# maxwell.net
KiCad netlist of a schematic drawn in EAGLE
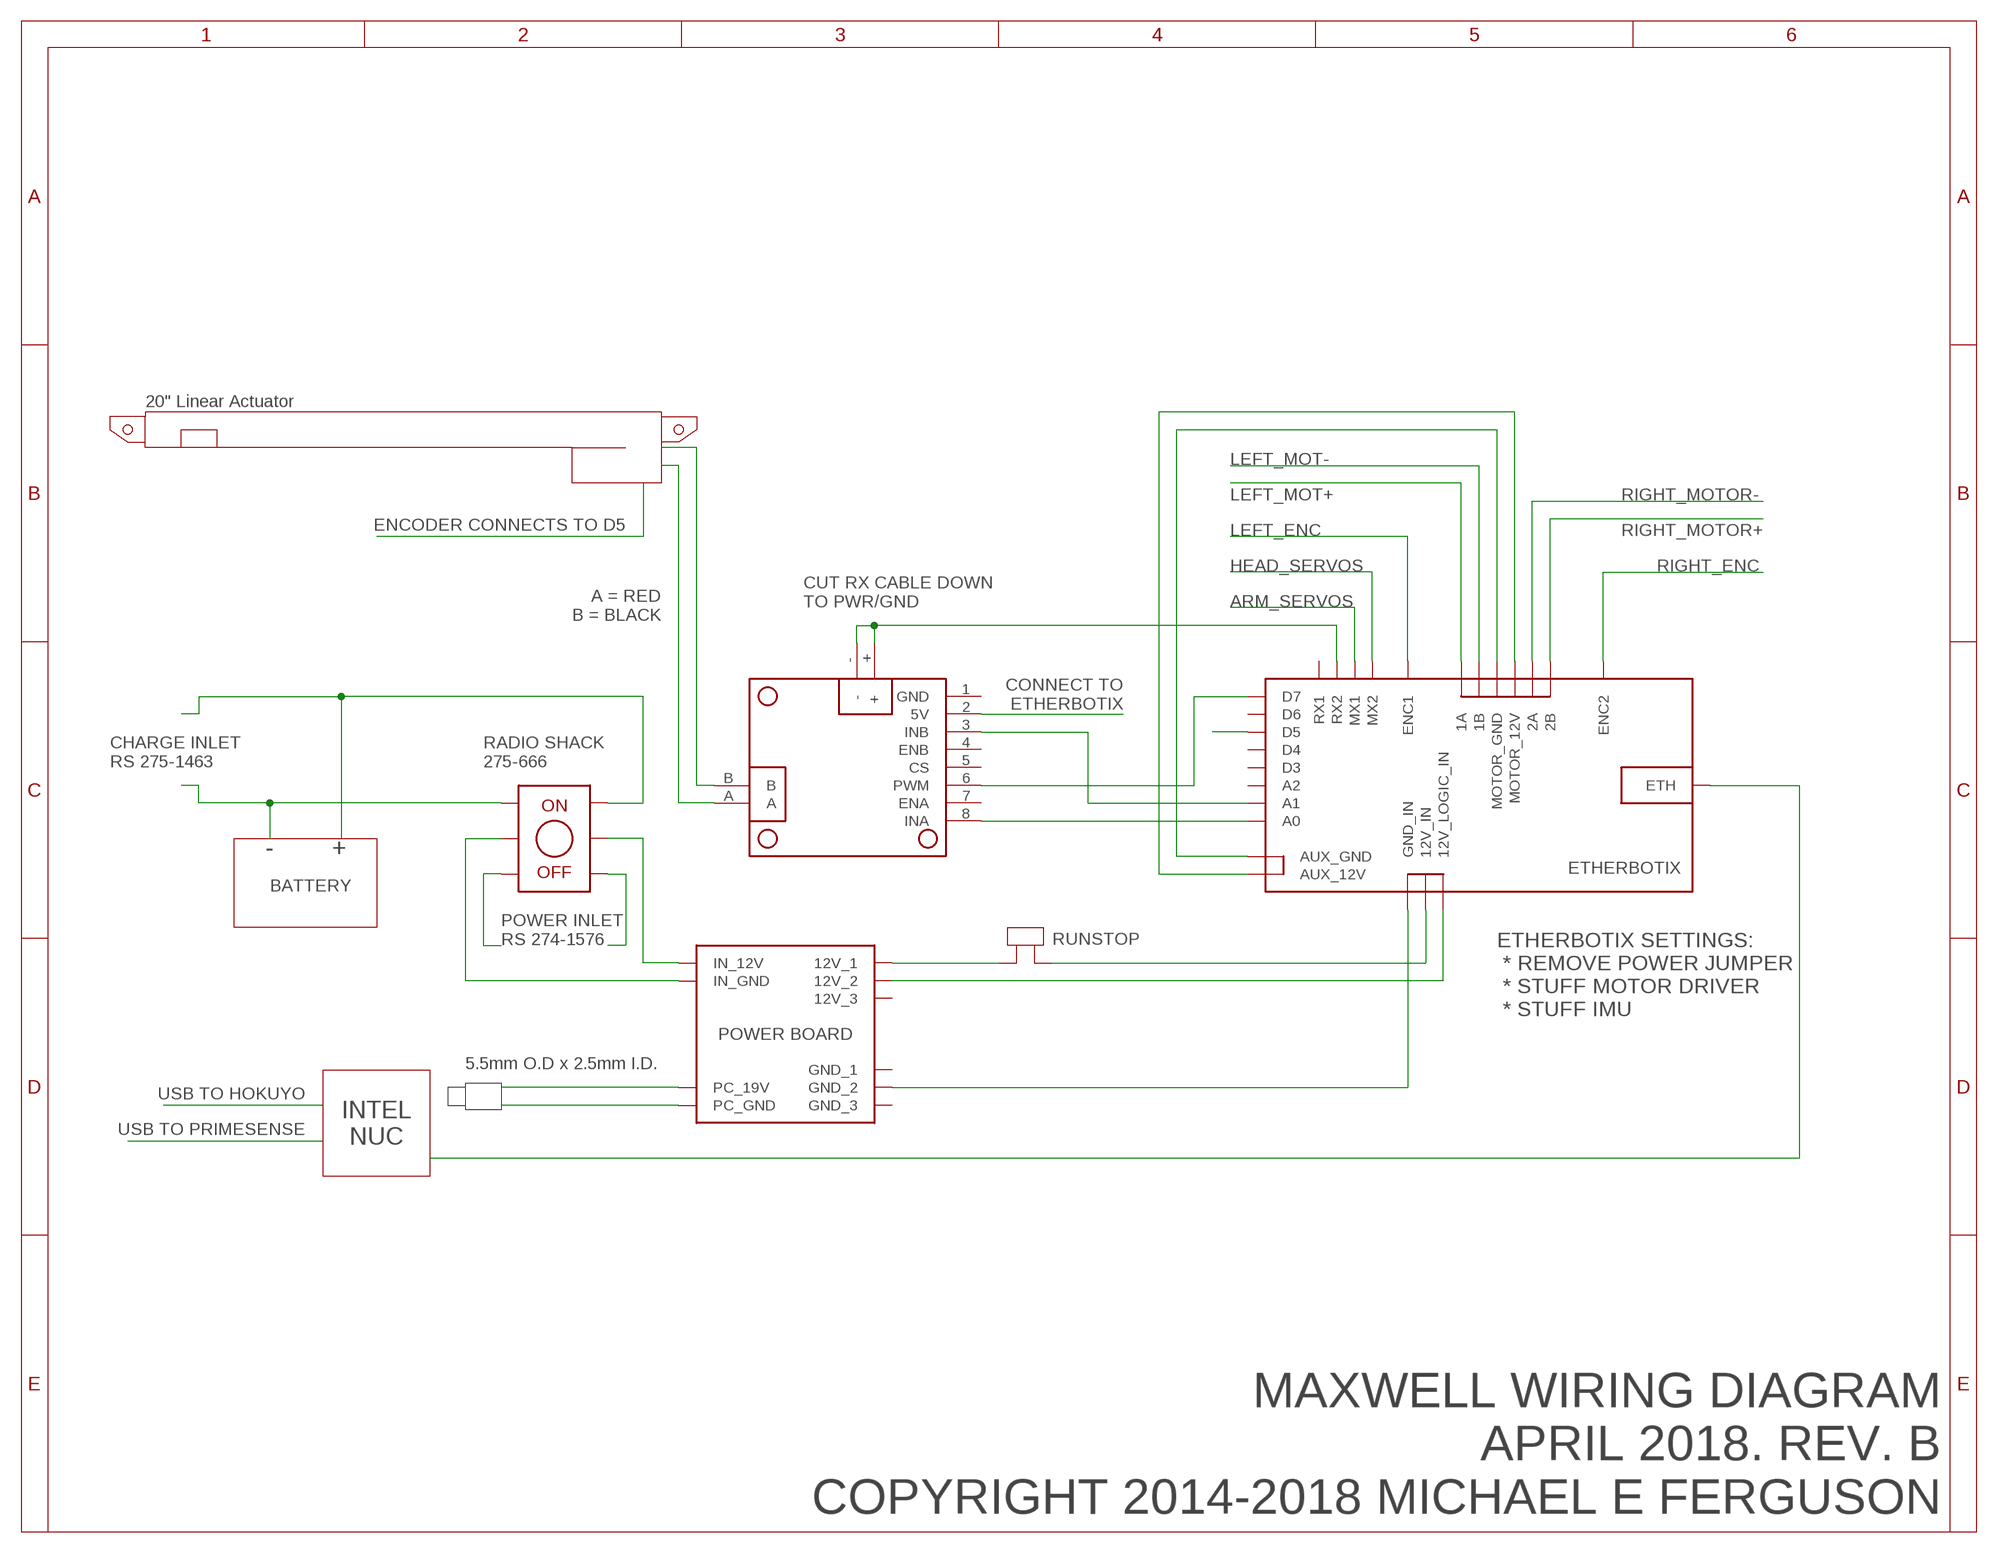
[diagram p0: schematic, sheet 1]

(export (version "E")
  (design (tool "Eeschema 10.0.6"))
  (components
    (comp (ref "U$1")
      (value "ETHERBOTIX")
      (footprint "eagle-import:CRAP")
      (libsource (lib "eagle-import") (part "ETHERBOTIX"))
    )
    (comp (ref "U$2")
      (value "MAXWELL_POWERBOARD")
      (footprint "eagle-import:CRAP")
      (libsource (lib "eagle-import") (part "MAXWELL_POWERBOARD"))
    )
    (comp (ref "U$3")
      (value "RS275-666")
      (footprint "eagle-import:CRAP")
      (libsource (lib "eagle-import") (part "RS275-666"))
    )
    (comp (ref "U$4")
      (value "MD01B")
      (footprint "eagle-import:MD01B")
      (libsource (lib "eagle-import") (part "MD01B"))
    )
  )
  (nets
    (net (code "1") (name "/ARM_SERVOS") (class "Default")
      (node (ref "U$1") (pin "P$23") (pinfunction "MX1_P$23") (pintype "bidirectional"))
    )
    (net (code "2") (name "/HEAD_SERVOS") (class "Default")
      (node (ref "U$1") (pin "P$24") (pinfunction "MX2_P$24") (pintype "bidirectional"))
    )
    (net (code "3") (name "/LEFT_ENC") (class "Default")
      (node (ref "U$1") (pin "P$17") (pinfunction "ENC1_P$17") (pintype "bidirectional"))
    )
    (net (code "4") (name "/LEFT_MOT+") (class "Default")
      (node (ref "U$1") (pin "P$1") (pinfunction "1A_P$1") (pintype "bidirectional"))
    )
    (net (code "5") (name "/LEFT_MOT-") (class "Default")
      (node (ref "U$1") (pin "P$2") (pinfunction "1B_P$2") (pintype "bidirectional"))
    )
    (net (code "6") (name "/RIGHT_ENC") (class "Default")
      (node (ref "U$1") (pin "P$18") (pinfunction "ENC2_P$18") (pintype "bidirectional"))
    )
    (net (code "7") (name "/RIGHT_MOTOR+") (class "Default")
      (node (ref "U$1") (pin "P$4") (pinfunction "2B_P$4") (pintype "bidirectional"))
    )
    (net (code "8") (name "/RIGHT_MOTOR-") (class "Default")
      (node (ref "U$1") (pin "P$3") (pinfunction "2A_P$3") (pintype "bidirectional"))
    )
    (net (code "9") (name "Net-(U$1-12V_LOGIC_IN)") (class "Default")
      (node (ref "U$1") (pin "P$6") (pinfunction "12V_LOGIC_IN_P$6") (pintype "bidirectional"))
      (node (ref "U$2") (pin "P$2") (pinfunction "12V_2_P$2") (pintype "bidirectional"))
    )
    (net (code "10") (name "Net-(U$1-A0)") (class "Default")
      (node (ref "U$1") (pin "P$7") (pinfunction "A0_P$7") (pintype "bidirectional"))
      (node (ref "U$4") (pin "8") (pinfunction "INA_8") (pintype "bidirectional"))
    )
    (net (code "11") (name "Net-(U$1-A1)") (class "Default")
      (node (ref "U$1") (pin "P$8") (pinfunction "A1_P$8") (pintype "bidirectional"))
      (node (ref "U$4") (pin "3") (pinfunction "INB_3") (pintype "bidirectional"))
    )
    (net (code "12") (name "Net-(U$1-AUX_12V)") (class "Default")
      (node (ref "U$1") (pin "P$10") (pinfunction "AUX_12V_P$10") (pintype "bidirectional"))
      (node (ref "U$1") (pin "P$21") (pinfunction "MOTOR_12V_P$21") (pintype "bidirectional"))
    )
    (net (code "13") (name "Net-(U$1-AUX_GND)") (class "Default")
      (node (ref "U$1") (pin "P$11") (pinfunction "AUX_GND_P$11") (pintype "bidirectional"))
      (node (ref "U$1") (pin "P$22") (pinfunction "MOTOR_GND_P$22") (pintype "bidirectional"))
    )
    (net (code "14") (name "Net-(U$1-D7)") (class "Default")
      (node (ref "U$1") (pin "P$16") (pinfunction "D7_P$16") (pintype "bidirectional"))
      (node (ref "U$4") (pin "6") (pinfunction "PWM_6") (pintype "bidirectional"))
    )
    (net (code "15") (name "Net-(U$1-GND_IN)") (class "Default")
      (node (ref "U$1") (pin "P$20") (pinfunction "GND_IN_P$20") (pintype "bidirectional"))
      (node (ref "U$2") (pin "P$5") (pinfunction "GND_2_P$5") (pintype "bidirectional"))
    )
    (net (code "16") (name "Net-(U$1-RX2)") (class "Default")
      (node (ref "U$1") (pin "P$26") (pinfunction "RX2_P$26") (pintype "bidirectional"))
      (node (ref "U$4") (pin "+") (pinfunction "+_+") (pintype "bidirectional"))
      (node (ref "U$4") (pin "-") (pinfunction "-_-") (pintype "bidirectional"))
    )
    (net (code "17") (name "Net-(U$2-IN_12V)") (class "Default")
      (node (ref "U$2") (pin "P$7") (pinfunction "IN_12V_P$7") (pintype "bidirectional"))
      (node (ref "U$3") (pin "P$4") (pinfunction "B_P$4") (pintype "bidirectional"))
    )
    (net (code "18") (name "Net-(U$2-IN_GND)") (class "Default")
      (node (ref "U$2") (pin "P$8") (pinfunction "IN_GND_P$8") (pintype "bidirectional"))
      (node (ref "U$3") (pin "P$1") (pinfunction "A_P$1") (pintype "bidirectional"))
    )
    (net (code "19") (name "unconnected-(U$1-12V_IN-PadP$5)") (class "Default")
      (node (ref "U$1") (pin "P$5") (pinfunction "12V_IN_P$5") (pintype "bidirectional"))
    )
    (net (code "20") (name "unconnected-(U$1-A2-PadP$9)") (class "Default")
      (node (ref "U$1") (pin "P$9") (pinfunction "A2_P$9") (pintype "bidirectional"))
    )
    (net (code "21") (name "unconnected-(U$1-D3-PadP$12)") (class "Default")
      (node (ref "U$1") (pin "P$12") (pinfunction "D3_P$12") (pintype "bidirectional"))
    )
    (net (code "22") (name "unconnected-(U$1-D4-PadP$13)") (class "Default")
      (node (ref "U$1") (pin "P$13") (pinfunction "D4_P$13") (pintype "bidirectional"))
    )
    (net (code "23") (name "unconnected-(U$1-D5-PadP$14)") (class "Default")
      (node (ref "U$1") (pin "P$14") (pinfunction "D5_P$14") (pintype "bidirectional"))
    )
    (net (code "24") (name "unconnected-(U$1-D6-PadP$15)") (class "Default")
      (node (ref "U$1") (pin "P$15") (pinfunction "D6_P$15") (pintype "bidirectional"))
    )
    (net (code "25") (name "unconnected-(U$1-ETH-PadP$19)") (class "Default")
      (node (ref "U$1") (pin "P$19") (pinfunction "ETH_P$19") (pintype "bidirectional"))
    )
    (net (code "26") (name "unconnected-(U$1-RX1-PadP$25)") (class "Default")
      (node (ref "U$1") (pin "P$25") (pinfunction "RX1_P$25") (pintype "bidirectional"))
    )
    (net (code "27") (name "unconnected-(U$2-12V_1-PadP$1)") (class "Default")
      (node (ref "U$2") (pin "P$1") (pinfunction "12V_1_P$1") (pintype "bidirectional"))
    )
    (net (code "28") (name "unconnected-(U$2-12V_3-PadP$3)") (class "Default")
      (node (ref "U$2") (pin "P$3") (pinfunction "12V_3_P$3") (pintype "bidirectional"))
    )
    (net (code "29") (name "unconnected-(U$2-GND_1-PadP$4)") (class "Default")
      (node (ref "U$2") (pin "P$4") (pinfunction "GND_1_P$4") (pintype "bidirectional"))
    )
    (net (code "30") (name "unconnected-(U$2-GND_3-PadP$6)") (class "Default")
      (node (ref "U$2") (pin "P$6") (pinfunction "GND_3_P$6") (pintype "bidirectional"))
    )
    (net (code "31") (name "unconnected-(U$2-PC_19V-PadP$9)") (class "Default")
      (node (ref "U$2") (pin "P$9") (pinfunction "PC_19V_P$9") (pintype "bidirectional"))
    )
    (net (code "32") (name "unconnected-(U$2-PC_GND-PadP$10)") (class "Default")
      (node (ref "U$2") (pin "P$10") (pinfunction "PC_GND_P$10") (pintype "bidirectional"))
    )
    (net (code "33") (name "unconnected-(U$3-A0-PadP$2)") (class "Default")
      (node (ref "U$3") (pin "P$2") (pinfunction "A0_P$2") (pintype "bidirectional"))
    )
    (net (code "34") (name "unconnected-(U$3-A1-PadP$3)") (class "Default")
      (node (ref "U$3") (pin "P$3") (pinfunction "A1_P$3") (pintype "bidirectional"))
    )
    (net (code "35") (name "unconnected-(U$3-B0-PadP$5)") (class "Default")
      (node (ref "U$3") (pin "P$5") (pinfunction "B0_P$5") (pintype "bidirectional"))
    )
    (net (code "36") (name "unconnected-(U$3-B1-PadP$6)") (class "Default")
      (node (ref "U$3") (pin "P$6") (pinfunction "B1_P$6") (pintype "bidirectional"))
    )
    (net (code "37") (name "unconnected-(U$4-5V-Pad2)") (class "Default")
      (node (ref "U$4") (pin "2") (pinfunction "5V_2") (pintype "bidirectional"))
    )
    (net (code "38") (name "unconnected-(U$4-CS-Pad5)") (class "Default")
      (node (ref "U$4") (pin "5") (pinfunction "CS_5") (pintype "bidirectional"))
    )
    (net (code "39") (name "unconnected-(U$4-ENA-Pad7)") (class "Default")
      (node (ref "U$4") (pin "7") (pinfunction "ENA_7") (pintype "bidirectional"))
    )
    (net (code "40") (name "unconnected-(U$4-ENB-Pad4)") (class "Default")
      (node (ref "U$4") (pin "4") (pinfunction "ENB_4") (pintype "bidirectional"))
    )
    (net (code "41") (name "unconnected-(U$4-GND-Pad1)") (class "Default")
      (node (ref "U$4") (pin "1") (pinfunction "GND_1") (pintype "bidirectional"))
    )
    (net (code "42") (name "unconnected-(U$4-PadA)") (class "Default")
      (node (ref "U$4") (pin "A") (pinfunction "A_A") (pintype "bidirectional"))
    )
    (net (code "43") (name "unconnected-(U$4-PadB)") (class "Default")
      (node (ref "U$4") (pin "B") (pinfunction "B_B") (pintype "bidirectional"))
    )
  )
)
